# MCP73832_BOB.net
KiCad netlist of a schematic drawn in EAGLE
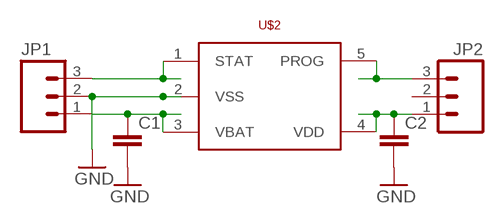
[diagram p0: schematic, sheet 1]

(export (version "E")
  (design (tool "Eeschema 10.0.6"))
  (components
    (comp (ref "C1")
      (value "CAP1206")
      (footprint "eagle-import:1206")
      (libsource (lib "eagle-import") (part "CAP1206"))
    )
    (comp (ref "C2")
      (value "CAP1206")
      (footprint "eagle-import:1206")
      (libsource (lib "eagle-import") (part "CAP1206"))
    )
    (comp (ref "JP1")
      (value "M03LOCK")
      (footprint "eagle-import:1X03_LOCK")
      (libsource (lib "eagle-import") (part "M03LOCK"))
    )
    (comp (ref "JP2")
      (value "M03LOCK")
      (footprint "eagle-import:1X03_LOCK")
      (libsource (lib "eagle-import") (part "M03LOCK"))
    )
    (comp (ref "U$2")
      (value "MCP73832")
      (footprint "eagle-import:SOT-23(OT)5_LEAD")
      (libsource (lib "eagle-import") (part "MCP73832"))
    )
  )
  (nets
    (net (code "1") (name "GND") (class "Default")
      (node (ref "C1") (pin "2") (pinfunction "2_2") (pintype "passive"))
      (node (ref "C2") (pin "2") (pinfunction "2_2") (pintype "passive"))
      (node (ref "JP1") (pin "2") (pinfunction "2_2") (pintype "passive"))
      (node (ref "U$2") (pin "2") (pinfunction "VSS_2") (pintype "power_in"))
    )
    (net (code "2") (name "Net-(U$2-PROG)") (class "Default")
      (node (ref "JP2") (pin "3") (pinfunction "3_3") (pintype "passive"))
      (node (ref "U$2") (pin "5") (pinfunction "PROG_5") (pintype "open_collector"))
    )
    (net (code "3") (name "Net-(U$2-STAT)") (class "Default")
      (node (ref "JP1") (pin "3") (pinfunction "3_3") (pintype "passive"))
      (node (ref "U$2") (pin "1") (pinfunction "STAT_1") (pintype "output"))
    )
    (net (code "4") (name "Net-(U$2-VBAT)") (class "Default")
      (node (ref "C1") (pin "1") (pinfunction "1_1") (pintype "passive"))
      (node (ref "JP1") (pin "1") (pinfunction "1_1") (pintype "passive"))
      (node (ref "U$2") (pin "3") (pinfunction "VBAT_3") (pintype "power_in"))
    )
    (net (code "5") (name "Net-(U$2-VDD)") (class "Default")
      (node (ref "C2") (pin "1") (pinfunction "1_1") (pintype "passive"))
      (node (ref "JP2") (pin "1") (pinfunction "1_1") (pintype "passive"))
      (node (ref "U$2") (pin "4") (pinfunction "VDD_4") (pintype "power_in"))
    )
    (net (code "6") (name "unconnected-(JP2-Pad2)") (class "Default")
      (node (ref "JP2") (pin "2") (pinfunction "2_2") (pintype "passive"))
    )
  )
)
